# Control_Board.net
KiCad netlist of a schematic drawn in Altium Designer
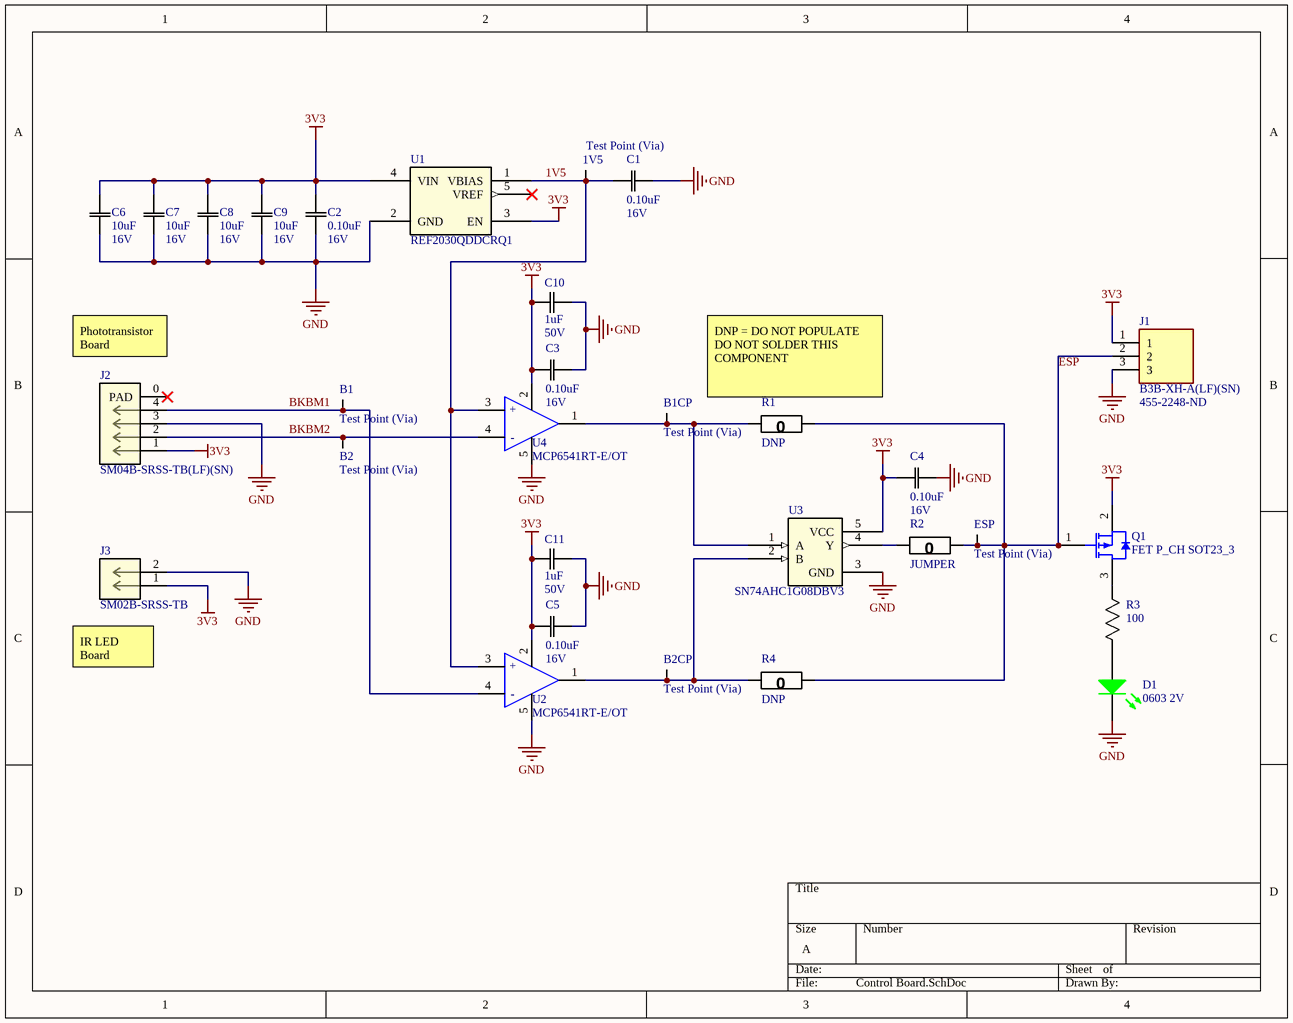
[diagram p0: Control Board.SchDoc]

(export (version "E")
  (design (tool "Eeschema 10.0.6"))
  (components
    (comp (ref "1V5")
      (value "Test Point (Via)")
      (footprint "TP")
      (libsource (lib "IC_Library") (part "Test Point (Via)"))
    )
    (comp (ref "B1")
      (value "Test Point (Via)")
      (footprint "TP")
      (libsource (lib "IC_Library") (part "Test Point (Via)"))
    )
    (comp (ref "B1CP")
      (value "Test Point (Via)")
      (footprint "TP")
      (libsource (lib "IC_Library") (part "Test Point (Via)"))
    )
    (comp (ref "B2")
      (value "Test Point (Via)")
      (footprint "TP")
      (libsource (lib "IC_Library") (part "Test Point (Via)"))
    )
    (comp (ref "B2CP")
      (value "Test Point (Via)")
      (footprint "TP")
      (libsource (lib "IC_Library") (part "Test Point (Via)"))
    )
    (comp (ref "C1")
      (value "0.10uF")
      (footprint "0603")
      (description "CAP CER 0.10UF 16V X5R 0603")
      (fields
        (field (name "TOLERANCE") "10%")
        (field (name "RATING") "16V")
        (field (name "PART NUMBER") "CAP 0.10uF 16V")
      )
      (libsource (lib "capacitor_library") (part "CAP 0.10uF 16V"))
    )
    (comp (ref "C2")
      (value "0.10uF")
      (footprint "0603")
      (description "CAP CER 0.10UF 16V X5R 0603")
      (fields
        (field (name "TOLERANCE") "10%")
        (field (name "RATING") "16V")
        (field (name "PART NUMBER") "CAP 0.10uF 16V")
      )
      (libsource (lib "capacitor_library") (part "CAP 0.10uF 16V"))
    )
    (comp (ref "C3")
      (value "0.10uF")
      (footprint "0603")
      (description "CAP CER 0.10UF 16V X5R 0603")
      (fields
        (field (name "TOLERANCE") "10%")
        (field (name "RATING") "16V")
        (field (name "PART NUMBER") "CAP 0.10uF 16V")
      )
      (libsource (lib "capacitor_library") (part "CAP 0.10uF 16V"))
    )
    (comp (ref "C4")
      (value "0.10uF")
      (footprint "0603")
      (description "CAP CER 0.10UF 16V X5R 0603")
      (fields
        (field (name "TOLERANCE") "10%")
        (field (name "RATING") "16V")
        (field (name "PART NUMBER") "CAP 0.10uF 16V")
      )
      (libsource (lib "capacitor_library") (part "CAP 0.10uF 16V"))
    )
    (comp (ref "C5")
      (value "0.10uF")
      (footprint "0603")
      (description "CAP CER 0.10UF 16V X5R 0603")
      (fields
        (field (name "TOLERANCE") "10%")
        (field (name "RATING") "16V")
        (field (name "PART NUMBER") "CAP 0.10uF 16V")
      )
      (libsource (lib "capacitor_library") (part "CAP 0.10uF 16V"))
    )
    (comp (ref "C6")
      (value "10uF")
      (footprint "0603")
      (description "CAP CER 10UF 16V X5R 0603/0805")
      (fields
        (field (name "TOLERANCE") "10%")
        (field (name "RATING") "16V")
        (field (name "PART NUMBER") "CAP 10uF 16V")
      )
      (libsource (lib "capacitor_library") (part "CAP 10uF 16V"))
    )
    (comp (ref "C7")
      (value "10uF")
      (footprint "0603")
      (description "CAP CER 10UF 16V X5R 0603/0805")
      (fields
        (field (name "TOLERANCE") "10%")
        (field (name "RATING") "16V")
        (field (name "PART NUMBER") "CAP 10uF 16V")
      )
      (libsource (lib "capacitor_library") (part "CAP 10uF 16V"))
    )
    (comp (ref "C8")
      (value "10uF")
      (footprint "0603")
      (description "CAP CER 10UF 16V X5R 0603/0805")
      (fields
        (field (name "TOLERANCE") "10%")
        (field (name "RATING") "16V")
        (field (name "PART NUMBER") "CAP 10uF 16V")
      )
      (libsource (lib "capacitor_library") (part "CAP 10uF 16V"))
    )
    (comp (ref "C9")
      (value "10uF")
      (footprint "0603")
      (description "CAP CER 10UF 16V X5R 0603/0805")
      (fields
        (field (name "TOLERANCE") "10%")
        (field (name "RATING") "16V")
        (field (name "PART NUMBER") "CAP 10uF 16V")
      )
      (libsource (lib "capacitor_library") (part "CAP 10uF 16V"))
    )
    (comp (ref "C10")
      (value "1uF")
      (footprint "0603")
      (description "Default Symbol for Capacitors")
      (fields
        (field (name "RATING") "50V")
        (field (name "PART NUMBER") "CAP 1uF 50V")
        (field (name "TOLERANCE") "10%")
      )
      (libsource (lib "capacitor_library") (part "CAP_Default"))
    )
    (comp (ref "C11")
      (value "1uF")
      (footprint "0603")
      (description "Default Symbol for Capacitors")
      (fields
        (field (name "RATING") "50V")
        (field (name "PART NUMBER") "CAP 1uF 50V")
        (field (name "TOLERANCE") "10%")
      )
      (libsource (lib "capacitor_library") (part "CAP_Default"))
    )
    (comp (ref "D1")
      (value "0603 2V")
      (footprint "0603 - LED")
      (description "LED Uni-Color Green 574nm 2-Pin Chip LED T/R")
      (fields (field (name "PART NUMBER") "LED GREEN SMD 0603"))
      (libsource (lib "Diode_Library") (part "LED GREEN SMD 0603"))
    )
    (comp (ref "ESP")
      (value "Test Point (Via)")
      (footprint "TP")
      (libsource (lib "IC_Library") (part "Test Point (Via)"))
    )
    (comp (ref "J1")
      (value "B3B-XH-A(LF)(SN)")
      (footprint "JST_B3B-XH-A(LF)(SN)")
      (description "Connector Header Through Hole 3 position 0.098 (2.50mm)")
      (fields
        (field (name "MF") "JST Sales")
        (field (name "SUPPLIER PART NUMBER 1") "455-2248-ND")
        (field (name "PART NUMBER") "CN HDR 3POS JST XH")
      )
      (libsource (lib "Connector_Library") (part "CN HDR 3POS JST XH"))
    )
    (comp (ref "J2")
      (value "SM04B-SRSS-TB(LF)(SN)")
      (footprint "CONN_SM04B_JST")
      (description "CONN HEADER SMD R/A 4POS 1MM")
      (fields
        (field (name "PART NUMBER") "CN HDR 4POS JST SH_SR")
        (field (name "COPYRIGHT") "Copyright (C) 2023 Ultra Librarian. All rights reserved.")
      )
      (libsource (lib "Connector_Library") (part "CN HDR 4POS JST SH_SR"))
    )
    (comp (ref "J3")
      (value "SM02B-SRSS-TB")
      (footprint "SM02B-SRSS-TB(LF)(SN)")
      (description "No Description Available")
      (fields
        (field (name "PART NUMBER") "CN HDR 2POS 90 JST SH")
        (field (name "COPYRIGHT") "Copyright (C) 2023 Ultra Librarian. All rights reserved.")
      )
      (libsource (lib "Connector_Library") (part "CN HDR 2POS 90 JST SH"))
    )
    (comp (ref "Q1")
      (value "FET P_CH SOT23_3")
      (footprint "SOT-23A-3:SOT-23A-3")
      (description "P-Channel MOSFET General Purpose P-CH SOT23-3")
      (fields (field (name "PART NUMBER") "MOSFET P-CH CJ2305"))
      (libsource (lib "Transistor_Library") (part "FET P_CH SOT23_3"))
    )
    (comp (ref "R1")
      (value "DNP")
      (footprint "0603:0603")
      (description "RES SMD 0 OHM JUMPER GENERIC 0603")
      (fields (field (name "PART NUMBER") "RES 0 JUMPER"))
      (libsource (lib "Resistor_Library") (part "RES 0 JUMPER"))
    )
    (comp (ref "R2")
      (value "JUMPER")
      (footprint "0603:0603")
      (description "RES SMD 0 OHM JUMPER GENERIC 0603")
      (fields (field (name "PART NUMBER") "RES 0 JUMPER"))
      (libsource (lib "Resistor_Library") (part "RES 0 JUMPER"))
    )
    (comp (ref "R3")
      (value "100")
      (footprint "0603")
      (description "Default Resistor Symbol")
      (fields (field (name "TOLERANCE") "5%") (field (name "PART NUMBER") "RES 100.0 1/8W - 5%"))
      (libsource (lib "Resistor_Library") (part "RES_DEFAULT"))
    )
    (comp (ref "R4")
      (value "DNP")
      (footprint "0603:0603")
      (description "RES SMD 0 OHM JUMPER GENERIC 0603")
      (fields (field (name "PART NUMBER") "RES 0 JUMPER"))
      (libsource (lib "Resistor_Library") (part "RES 0 JUMPER"))
    )
    (comp (ref "U1")
      (value "REF2030QDDCRQ1")
      (footprint "SOT-23-5_MC_MCH-L")
      (description "Series Voltage Reference IC Fixed 1.5V, 3V V ±0.05% 20 mA SOT-23-THIN")
      (fields
        (field (name "MANUFACTURER_PART_NUMBER") "SN74AHC1G08DBV3")
        (field (name "COPYRIGHT") "Copyright (C) 2023 Ultra Librarian. All rights reserved.")
      )
      (libsource (lib "IC_Library") (part "REF2030QDDCRQ1"))
    )
    (comp (ref "U2")
      (value "MCP6541RT-E/OT")
      (footprint "SOT-23-5_MC_MCH-L")
      (description "IC COMP 1.6V SNGL P-P SOT23-5")
      (fields (field (name "PART NUMBER") "COMPARATOR MCP6541RT-EOT"))
      (libsource (lib "IC_Library") (part "COMPARATOR MCP6541RT-EOT"))
    )
    (comp (ref "U3")
      (value "SN74AHC1G08DBV3")
      (footprint "SOT-23-5_MC_MCH-L")
      (description "IC GATE AND 1CH 2-INP SOT23-5")
      (fields (field (name "COPYRIGHT") "Copyright (C) 2023 Ultra Librarian. All rights reserved."))
      (libsource (lib "IC_Library") (part "SN74AHC1G08DBV3"))
    )
    (comp (ref "U4")
      (value "MCP6541RT-E/OT")
      (footprint "SOT-23-5_MC_MCH-L")
      (description "IC COMP 1.6V SNGL P-P SOT23-5")
      (fields (field (name "PART NUMBER") "COMPARATOR MCP6541RT-EOT"))
      (libsource (lib "IC_Library") (part "COMPARATOR MCP6541RT-EOT"))
    )
  )
  (nets
    (net (code "1") (name "/1V5") (class "Default")
      (node (ref "1V5") (pin "1") (pinfunction "1_1") (pintype "passive"))
      (node (ref "C1") (pin "2") (pinfunction "C2_2") (pintype "passive"))
      (node (ref "U1") (pin "1") (pinfunction "VBIAS_1") (pintype "passive"))
      (node (ref "U2") (pin "3") (pinfunction "IN+_3") (pintype "tri_state"))
      (node (ref "U4") (pin "3") (pinfunction "IN+_3") (pintype "tri_state"))
    )
    (net (code "2") (name "/BKBM1") (class "Default")
      (node (ref "B1") (pin "1") (pinfunction "1_1") (pintype "passive"))
      (node (ref "J2") (pin "4") (pinfunction "4_4") (pintype "passive"))
      (node (ref "U2") (pin "4") (pinfunction "IN-_4") (pintype "tri_state"))
    )
    (net (code "3") (name "/BKBM2") (class "Default")
      (node (ref "B2") (pin "1") (pinfunction "1_1") (pintype "passive"))
      (node (ref "J2") (pin "2") (pinfunction "2_2") (pintype "passive"))
      (node (ref "U4") (pin "4") (pinfunction "IN-_4") (pintype "tri_state"))
    )
    (net (code "4") (name "/ESP") (class "Default")
      (node (ref "ESP") (pin "1") (pinfunction "1_1") (pintype "passive"))
      (node (ref "J1") (pin "2") (pinfunction "2_2") (pintype "passive"))
      (node (ref "Q1") (pin "1") (pinfunction "GATE_1") (pintype "passive"))
      (node (ref "R1") (pin "1") (pinfunction "R1_1") (pintype "passive"))
      (node (ref "R2") (pin "1") (pinfunction "R1_1") (pintype "passive"))
      (node (ref "R4") (pin "1") (pinfunction "R1_1") (pintype "passive"))
    )
    (net (code "5") (name "3V3") (class "Default")
      (node (ref "C10") (pin "1") (pinfunction "C1_1") (pintype "passive"))
      (node (ref "C11") (pin "1") (pinfunction "C1_1") (pintype "passive"))
      (node (ref "C2") (pin "1") (pinfunction "C1_1") (pintype "passive"))
      (node (ref "C3") (pin "2") (pinfunction "C2_2") (pintype "passive"))
      (node (ref "C4") (pin "2") (pinfunction "C2_2") (pintype "passive"))
      (node (ref "C5") (pin "2") (pinfunction "C2_2") (pintype "passive"))
      (node (ref "C6") (pin "2") (pinfunction "C2_2") (pintype "passive"))
      (node (ref "C7") (pin "2") (pinfunction "C2_2") (pintype "passive"))
      (node (ref "C8") (pin "2") (pinfunction "C2_2") (pintype "passive"))
      (node (ref "C9") (pin "2") (pinfunction "C2_2") (pintype "passive"))
      (node (ref "J1") (pin "1") (pinfunction "1_1") (pintype "passive"))
      (node (ref "J2") (pin "1") (pinfunction "1_1") (pintype "passive"))
      (node (ref "J3") (pin "1") (pinfunction "1_1") (pintype "passive"))
      (node (ref "Q1") (pin "2") (pinfunction "SOURCE_2") (pintype "passive"))
      (node (ref "U1") (pin "3") (pinfunction "EN_3") (pintype "power_in"))
      (node (ref "U1") (pin "4") (pinfunction "VIN_4") (pintype "power_in"))
      (node (ref "U2") (pin "2") (pinfunction "V+_2") (pintype "power_in"))
      (node (ref "U3") (pin "5") (pinfunction "VCC_5") (pintype "power_in"))
      (node (ref "U4") (pin "2") (pinfunction "V+_2") (pintype "power_in"))
    )
    (net (code "6") (name "GND") (class "Default")
      (node (ref "C1") (pin "1") (pinfunction "C1_1") (pintype "passive"))
      (node (ref "C10") (pin "2") (pinfunction "C2_2") (pintype "passive"))
      (node (ref "C11") (pin "2") (pinfunction "C2_2") (pintype "passive"))
      (node (ref "C2") (pin "2") (pinfunction "C2_2") (pintype "passive"))
      (node (ref "C3") (pin "1") (pinfunction "C1_1") (pintype "passive"))
      (node (ref "C4") (pin "1") (pinfunction "C1_1") (pintype "passive"))
      (node (ref "C5") (pin "1") (pinfunction "C1_1") (pintype "passive"))
      (node (ref "C6") (pin "1") (pinfunction "C1_1") (pintype "passive"))
      (node (ref "C7") (pin "1") (pinfunction "C1_1") (pintype "passive"))
      (node (ref "C8") (pin "1") (pinfunction "C1_1") (pintype "passive"))
      (node (ref "C9") (pin "1") (pinfunction "C1_1") (pintype "passive"))
      (node (ref "D1") (pin "2") (pinfunction "K_2") (pintype "passive"))
      (node (ref "J1") (pin "3") (pinfunction "3_3") (pintype "passive"))
      (node (ref "J2") (pin "3") (pinfunction "3_3") (pintype "passive"))
      (node (ref "J3") (pin "2") (pinfunction "2_2") (pintype "passive"))
      (node (ref "U1") (pin "2") (pinfunction "GND_2") (pintype "power_in"))
      (node (ref "U2") (pin "5") (pinfunction "V-_5") (pintype "power_in"))
      (node (ref "U3") (pin "3") (pinfunction "GND_3") (pintype "power_in"))
      (node (ref "U4") (pin "5") (pinfunction "V-_5") (pintype "power_in"))
    )
    (net (code "7") (name "Net-(D1-A)") (class "Default")
      (node (ref "D1") (pin "1") (pinfunction "A_1") (pintype "passive"))
      (node (ref "R3") (pin "1") (pinfunction "R1_1") (pintype "passive"))
    )
    (net (code "8") (name "Net-(Q1-DRAIN)") (class "Default")
      (node (ref "Q1") (pin "3") (pinfunction "DRAIN_3") (pintype "passive"))
      (node (ref "R3") (pin "2") (pinfunction "R2_2") (pintype "passive"))
    )
    (net (code "9") (name "Net-(R1-R2)") (class "Default")
      (node (ref "B1CP") (pin "1") (pinfunction "1_1") (pintype "passive"))
      (node (ref "R1") (pin "2") (pinfunction "R2_2") (pintype "passive"))
      (node (ref "U3") (pin "1") (pinfunction "A_1") (pintype "input"))
      (node (ref "U4") (pin "1") (pinfunction "OUT_1") (pintype "passive"))
    )
    (net (code "10") (name "Net-(R2-R2)") (class "Default")
      (node (ref "R2") (pin "2") (pinfunction "R2_2") (pintype "passive"))
      (node (ref "U3") (pin "4") (pinfunction "Y_4") (pintype "output"))
    )
    (net (code "11") (name "Net-(R4-R2)") (class "Default")
      (node (ref "B2CP") (pin "1") (pinfunction "1_1") (pintype "passive"))
      (node (ref "R4") (pin "2") (pinfunction "R2_2") (pintype "passive"))
      (node (ref "U2") (pin "1") (pinfunction "OUT_1") (pintype "passive"))
      (node (ref "U3") (pin "2") (pinfunction "B_2") (pintype "input"))
    )
    (net (code "12") (name "unconnected-(J2-PAD-Pad0)") (class "Default")
      (node (ref "J2") (pin "0") (pinfunction "PAD_0") (pintype "passive+no_connect"))
    )
    (net (code "13") (name "unconnected-(U1-VREF-Pad5)") (class "Default")
      (node (ref "U1") (pin "5") (pinfunction "VREF_5") (pintype "output+no_connect"))
    )
  )
)
